# display-header.net
KiCad netlist of a schematic drawn in EAGLE
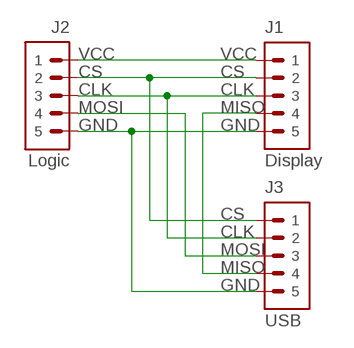
[diagram p0: schematic, sheet 1]

(export (version "E")
  (design (tool "Eeschema 10.0.6"))
  (components
    (comp (ref "J1")
      (value "Display")
      (footprint "eagle-import:89400-0520")
      (libsource (lib "eagle-import") (part "89400-0520"))
    )
    (comp (ref "J2")
      (value "Logic")
      (footprint "eagle-import:89400-0520")
      (libsource (lib "eagle-import") (part "89400-0520"))
    )
    (comp (ref "J3")
      (value "USB")
      (footprint "eagle-import:89400-0520")
      (libsource (lib "eagle-import") (part "89400-0520"))
    )
  )
  (nets
    (net (code "1") (name "/CLK") (class "Default")
      (node (ref "J1") (pin "3") (pinfunction "3_3") (pintype "passive"))
      (node (ref "J2") (pin "3") (pinfunction "3_3") (pintype "passive"))
      (node (ref "J3") (pin "2") (pinfunction "2_2") (pintype "passive"))
    )
    (net (code "2") (name "/CS") (class "Default")
      (node (ref "J1") (pin "2") (pinfunction "2_2") (pintype "passive"))
      (node (ref "J2") (pin "2") (pinfunction "2_2") (pintype "passive"))
      (node (ref "J3") (pin "1") (pinfunction "1_1") (pintype "passive"))
    )
    (net (code "3") (name "/GND") (class "Default")
      (node (ref "J1") (pin "5") (pinfunction "5_5") (pintype "passive"))
      (node (ref "J2") (pin "5") (pinfunction "5_5") (pintype "passive"))
      (node (ref "J3") (pin "5") (pinfunction "5_5") (pintype "passive"))
    )
    (net (code "4") (name "/MISO") (class "Default")
      (node (ref "J1") (pin "4") (pinfunction "4_4") (pintype "passive"))
      (node (ref "J3") (pin "4") (pinfunction "4_4") (pintype "passive"))
    )
    (net (code "5") (name "/MOSI") (class "Default")
      (node (ref "J2") (pin "4") (pinfunction "4_4") (pintype "passive"))
      (node (ref "J3") (pin "3") (pinfunction "3_3") (pintype "passive"))
    )
    (net (code "6") (name "/VCC") (class "Default")
      (node (ref "J1") (pin "1") (pinfunction "1_1") (pintype "passive"))
      (node (ref "J2") (pin "1") (pinfunction "1_1") (pintype "passive"))
    )
  )
)
